# masterUnit.net
KiCad netlist of a schematic drawn in Altium Designer
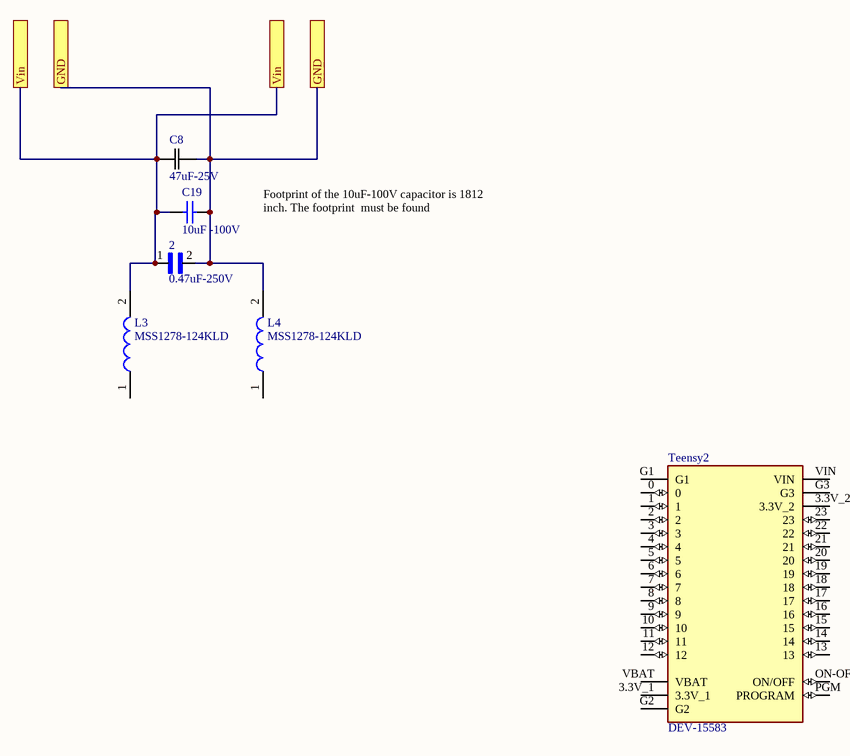
[diagram p0: masterUnit.SchDoc]

(export (version "E")
  (design (tool "Eeschema 10.0.6"))
  (components
    (comp (ref "2")
      (value "0.47uF-250V")
      (footprint "CAPC3326X280N")
      (fields (field (name "MP") "C1210X474KARACAUTO") (field (name "MF") "{'manufacturer': u'KEMET'}"))
      (libsource (lib "GIGUL") (part "C1210X474KARACAUTO"))
    )
    (comp (ref "C8")
      (value "47uF-25V")
      (description "No Description Available")
      (fields
        (field (name "MANUFACTURER_PART_NUMBER") "GRM31CR61E476ME44K")
        (field (name "COPYRIGHT") "Copyright (C) 2021 Ultra Librarian. All rights reserved.")
      )
      (libsource (lib "GIGUL") (part "GRM31CR61E476ME44K"))
    )
    (comp (ref "C19")
      (value "10uF -100V")
      (description "Capacitor")
      (fields (field (name "Comment") "Symbol"))
      (libsource (lib "GIGUL") (part "Symbol"))
    )
    (comp (ref "L3")
      (value "MSS1278-124KLD")
      (footprint "INDPM120120X805N")
      (description "Inductor")
      (libsource (lib "GIGUL") (part "MSS1278-124KLD"))
    )
    (comp (ref "L4")
      (value "MSS1278-124KLD")
      (footprint "INDPM120120X805N")
      (description "Inductor")
      (libsource (lib "GIGUL") (part "MSS1278-124KLD"))
    )
    (comp (ref "Teensy2")
      (value "DEV-15583")
      (footprint "MODULE_DEV-15583")
      (description "RT1062 Teensy 4.0 i.MX ARMÂ® CortexÂ®-M7 MPU Embedded Evaluation Board")
      (fields
        (field (name "MF") "SparkFun Electronics")
        (field (name "DIGI-KEY_PART_NUMBER") "1568-DEV-15583-ND")
      )
      (libsource (lib "GIGUL") (part "DEV-15583"))
    )
  )
  (nets
    (net (code "1") (name "/GND") (class "Default")
      (node (ref "2") (pin "2") (pinfunction "2_2") (pintype "passive"))
      (node (ref "C19") (pin "2") (pinfunction "2_2") (pintype "passive"))
      (node (ref "C8") (pin "2") (pinfunction "2_2") (pintype "passive"))
      (node (ref "L4") (pin "2") (pinfunction "2_2") (pintype "passive"))
    )
    (net (code "2") (name "/Vin") (class "Default")
      (node (ref "2") (pin "1") (pinfunction "1_1") (pintype "passive"))
      (node (ref "C19") (pin "1") (pinfunction "1_1") (pintype "passive"))
      (node (ref "C8") (pin "1") (pinfunction "1_1") (pintype "passive"))
      (node (ref "L3") (pin "2") (pinfunction "2_2") (pintype "passive"))
    )
    (net (code "3") (name "unconnected-(L3-Pad1)") (class "Default")
      (node (ref "L3") (pin "1") (pinfunction "1_1") (pintype "passive"))
    )
    (net (code "4") (name "unconnected-(L4-Pad1)") (class "Default")
      (node (ref "L4") (pin "1") (pinfunction "1_1") (pintype "passive"))
    )
    (net (code "5") (name "unconnected-(Teensy2-ON{slash}OFF-PadON-OFF)") (class "Default")
      (node (ref "Teensy2") (pin "ON-OFF") (pinfunction "ON/OFF_ON-OFF") (pintype "bidirectional"))
    )
    (net (code "6") (name "unconnected-(Teensy2-PROGRAM-PadPGM)") (class "Default")
      (node (ref "Teensy2") (pin "PGM") (pinfunction "PROGRAM_PGM") (pintype "bidirectional"))
    )
    (net (code "7") (name "unconnected-(Teensy2-Pad0)") (class "Default")
      (node (ref "Teensy2") (pin "0") (pinfunction "0_0") (pintype "bidirectional"))
    )
    (net (code "8") (name "unconnected-(Teensy2-Pad1)") (class "Default")
      (node (ref "Teensy2") (pin "1") (pinfunction "1_1") (pintype "bidirectional"))
    )
    (net (code "9") (name "unconnected-(Teensy2-Pad2)") (class "Default")
      (node (ref "Teensy2") (pin "2") (pinfunction "2_2") (pintype "bidirectional"))
    )
    (net (code "10") (name "unconnected-(Teensy2-Pad3)") (class "Default")
      (node (ref "Teensy2") (pin "3") (pinfunction "3_3") (pintype "bidirectional"))
    )
    (net (code "11") (name "unconnected-(Teensy2-Pad3.3V_1)") (class "Default")
      (node (ref "Teensy2") (pin "3.3V_1") (pinfunction "3.3V_1_3.3V_1") (pintype "power_in"))
    )
    (net (code "12") (name "unconnected-(Teensy2-Pad3.3V_2)") (class "Default")
      (node (ref "Teensy2") (pin "3.3V_2") (pinfunction "3.3V_2_3.3V_2") (pintype "power_in"))
    )
    (net (code "13") (name "unconnected-(Teensy2-Pad4)") (class "Default")
      (node (ref "Teensy2") (pin "4") (pinfunction "4_4") (pintype "bidirectional"))
    )
    (net (code "14") (name "unconnected-(Teensy2-Pad5)") (class "Default")
      (node (ref "Teensy2") (pin "5") (pinfunction "5_5") (pintype "bidirectional"))
    )
    (net (code "15") (name "unconnected-(Teensy2-Pad6)") (class "Default")
      (node (ref "Teensy2") (pin "6") (pinfunction "6_6") (pintype "bidirectional"))
    )
    (net (code "16") (name "unconnected-(Teensy2-Pad7)") (class "Default")
      (node (ref "Teensy2") (pin "7") (pinfunction "7_7") (pintype "bidirectional"))
    )
    (net (code "17") (name "unconnected-(Teensy2-Pad8)") (class "Default")
      (node (ref "Teensy2") (pin "8") (pinfunction "8_8") (pintype "bidirectional"))
    )
    (net (code "18") (name "unconnected-(Teensy2-Pad9)") (class "Default")
      (node (ref "Teensy2") (pin "9") (pinfunction "9_9") (pintype "bidirectional"))
    )
    (net (code "19") (name "unconnected-(Teensy2-Pad10)") (class "Default")
      (node (ref "Teensy2") (pin "10") (pinfunction "10_10") (pintype "bidirectional"))
    )
    (net (code "20") (name "unconnected-(Teensy2-Pad11)") (class "Default")
      (node (ref "Teensy2") (pin "11") (pinfunction "11_11") (pintype "bidirectional"))
    )
    (net (code "21") (name "unconnected-(Teensy2-Pad12)") (class "Default")
      (node (ref "Teensy2") (pin "12") (pinfunction "12_12") (pintype "bidirectional"))
    )
    (net (code "22") (name "unconnected-(Teensy2-Pad13)") (class "Default")
      (node (ref "Teensy2") (pin "13") (pinfunction "13_13") (pintype "bidirectional"))
    )
    (net (code "23") (name "unconnected-(Teensy2-Pad14)") (class "Default")
      (node (ref "Teensy2") (pin "14") (pinfunction "14_14") (pintype "bidirectional"))
    )
    (net (code "24") (name "unconnected-(Teensy2-Pad15)") (class "Default")
      (node (ref "Teensy2") (pin "15") (pinfunction "15_15") (pintype "bidirectional"))
    )
    (net (code "25") (name "unconnected-(Teensy2-Pad16)") (class "Default")
      (node (ref "Teensy2") (pin "16") (pinfunction "16_16") (pintype "bidirectional"))
    )
    (net (code "26") (name "unconnected-(Teensy2-Pad17)") (class "Default")
      (node (ref "Teensy2") (pin "17") (pinfunction "17_17") (pintype "bidirectional"))
    )
    (net (code "27") (name "unconnected-(Teensy2-Pad18)") (class "Default")
      (node (ref "Teensy2") (pin "18") (pinfunction "18_18") (pintype "bidirectional"))
    )
    (net (code "28") (name "unconnected-(Teensy2-Pad19)") (class "Default")
      (node (ref "Teensy2") (pin "19") (pinfunction "19_19") (pintype "bidirectional"))
    )
    (net (code "29") (name "unconnected-(Teensy2-Pad20)") (class "Default")
      (node (ref "Teensy2") (pin "20") (pinfunction "20_20") (pintype "bidirectional"))
    )
    (net (code "30") (name "unconnected-(Teensy2-Pad21)") (class "Default")
      (node (ref "Teensy2") (pin "21") (pinfunction "21_21") (pintype "bidirectional"))
    )
    (net (code "31") (name "unconnected-(Teensy2-Pad22)") (class "Default")
      (node (ref "Teensy2") (pin "22") (pinfunction "22_22") (pintype "bidirectional"))
    )
    (net (code "32") (name "unconnected-(Teensy2-Pad23)") (class "Default")
      (node (ref "Teensy2") (pin "23") (pinfunction "23_23") (pintype "bidirectional"))
    )
    (net (code "33") (name "unconnected-(Teensy2-PadG1)") (class "Default")
      (node (ref "Teensy2") (pin "G1") (pinfunction "G1_G1") (pintype "power_in"))
    )
    (net (code "34") (name "unconnected-(Teensy2-PadG2)") (class "Default")
      (node (ref "Teensy2") (pin "G2") (pinfunction "G2_G2") (pintype "power_in"))
    )
    (net (code "35") (name "unconnected-(Teensy2-PadG3)") (class "Default")
      (node (ref "Teensy2") (pin "G3") (pinfunction "G3_G3") (pintype "power_in"))
    )
    (net (code "36") (name "unconnected-(Teensy2-PadVBAT)") (class "Default")
      (node (ref "Teensy2") (pin "VBAT") (pinfunction "VBAT_VBAT") (pintype "power_in"))
    )
    (net (code "37") (name "unconnected-(Teensy2-PadVIN)") (class "Default")
      (node (ref "Teensy2") (pin "VIN") (pinfunction "VIN_VIN") (pintype "power_in"))
    )
  )
)
